# MAX30102.net
KiCad netlist of a schematic drawn in Altium Designer
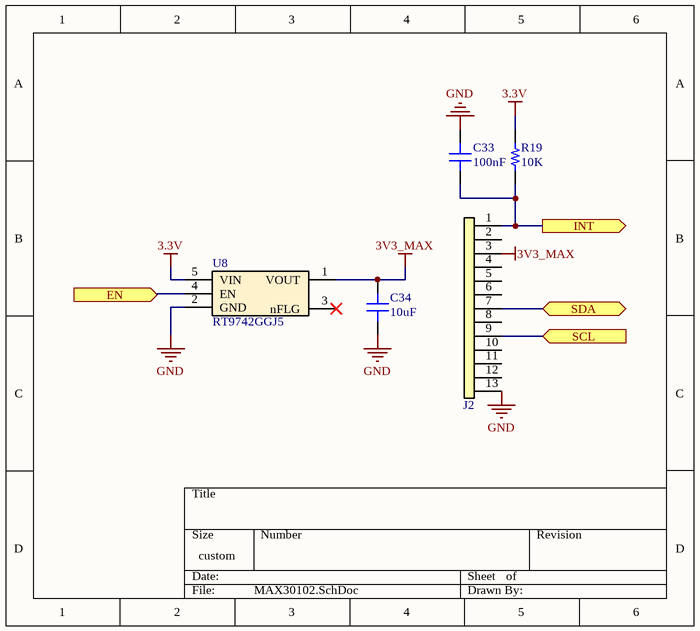
[diagram p0: MAX30102.SchDoc]

(export (version "E")
  (design (tool "Eeschema 10.0.6"))
  (components
    (comp (ref "C33")
      (value "100nF")
      (footprint "CAP 0603_1608")
      (description "SMT Capacitor")
      (libsource (lib "Capacitor") (part "Cap 0603"))
    )
    (comp (ref "C34")
      (value "10uF")
      (footprint "CAP 0603_1608")
      (description "SMT Capacitor")
      (libsource (lib "Capacitor") (part "Cap 0603"))
    )
    (comp (ref "J2")
      (value "FPC-13pos")
      (footprint "FPC-0.3mm-13pos")
      (description "FPC 0.3mm pitch 13pos")
      (libsource (lib "Salman_lib") (part "FPC-13pos"))
    )
    (comp (ref "R19")
      (value "10K")
      (footprint "RES 0603_1608")
      (description "SMT Resistor")
      (libsource (lib "Resistor") (part "Res 0603"))
    )
    (comp (ref "U8")
      (value "RT9742GGJ5")
      (footprint "SOT23-5L")
      (libsource (lib "Salman_lib") (part "RT9742GGJ5"))
    )
  )
  (nets
    (net (code "1") (name "/EN") (class "Default")
      (node (ref "U8") (pin "4") (pinfunction "EN_4") (pintype "passive"))
    )
    (net (code "2") (name "/INT") (class "Default")
      (node (ref "C33") (pin "1") (pinfunction "1_1") (pintype "passive"))
      (node (ref "J2") (pin "1") (pinfunction "1_1") (pintype "passive"))
      (node (ref "R19") (pin "2") (pinfunction "2_2") (pintype "passive"))
    )
    (net (code "3") (name "/SCL") (class "Default")
      (node (ref "J2") (pin "9") (pinfunction "9_9") (pintype "passive"))
    )
    (net (code "4") (name "/SDA") (class "Default")
      (node (ref "J2") (pin "7") (pinfunction "7_7") (pintype "passive"))
    )
    (net (code "5") (name "3.3V") (class "Default")
      (node (ref "R19") (pin "1") (pinfunction "1_1") (pintype "passive"))
      (node (ref "U8") (pin "5") (pinfunction "VIN_5") (pintype "passive"))
    )
    (net (code "6") (name "3V3_MAX") (class "Default")
      (node (ref "C34") (pin "2") (pinfunction "2_2") (pintype "passive"))
      (node (ref "J2") (pin "3") (pinfunction "3_3") (pintype "passive"))
      (node (ref "U8") (pin "1") (pinfunction "VOUT_1") (pintype "passive"))
    )
    (net (code "7") (name "GND") (class "Default")
      (node (ref "C33") (pin "2") (pinfunction "2_2") (pintype "passive"))
      (node (ref "C34") (pin "1") (pinfunction "1_1") (pintype "passive"))
      (node (ref "J2") (pin "13") (pinfunction "13_13") (pintype "passive"))
      (node (ref "U8") (pin "2") (pinfunction "GND_2") (pintype "passive"))
    )
    (net (code "8") (name "unconnected-(J2-Pad2)") (class "Default")
      (node (ref "J2") (pin "2") (pinfunction "2_2") (pintype "passive"))
    )
    (net (code "9") (name "unconnected-(J2-Pad4)") (class "Default")
      (node (ref "J2") (pin "4") (pinfunction "4_4") (pintype "passive"))
    )
    (net (code "10") (name "unconnected-(J2-Pad5)") (class "Default")
      (node (ref "J2") (pin "5") (pinfunction "5_5") (pintype "passive"))
    )
    (net (code "11") (name "unconnected-(J2-Pad6)") (class "Default")
      (node (ref "J2") (pin "6") (pinfunction "6_6") (pintype "passive"))
    )
    (net (code "12") (name "unconnected-(J2-Pad8)") (class "Default")
      (node (ref "J2") (pin "8") (pinfunction "8_8") (pintype "passive"))
    )
    (net (code "13") (name "unconnected-(J2-Pad10)") (class "Default")
      (node (ref "J2") (pin "10") (pinfunction "10_10") (pintype "passive"))
    )
    (net (code "14") (name "unconnected-(J2-Pad11)") (class "Default")
      (node (ref "J2") (pin "11") (pinfunction "11_11") (pintype "passive"))
    )
    (net (code "15") (name "unconnected-(J2-Pad12)") (class "Default")
      (node (ref "J2") (pin "12") (pinfunction "12_12") (pintype "passive"))
    )
    (net (code "16") (name "unconnected-(U8-nFLG-Pad3)") (class "Default")
      (node (ref "U8") (pin "3") (pinfunction "nFLG_3") (pintype "passive+no_connect"))
    )
  )
)
